# Sheet1.net
KiCad netlist of a schematic drawn in Altium Designer
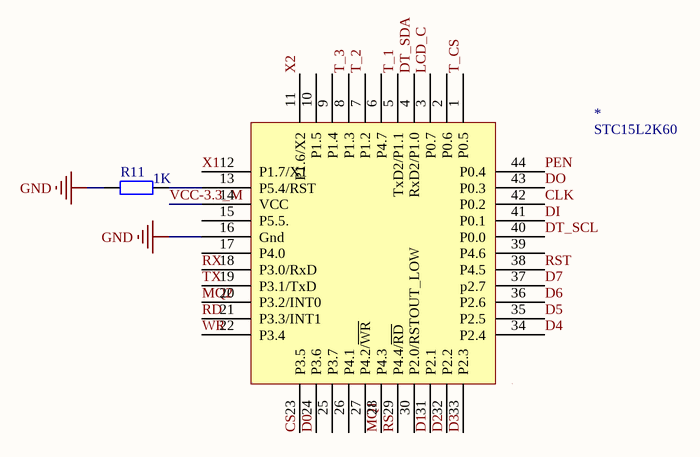
[diagram p0: Sheet1.SchDoc]

(export (version "E")
  (design (tool "Eeschema 10.0.6"))
  (components
    (comp (ref "*")
      (value "STC15L2K60")
      (description "STC15L,44pin")
      (libsource (lib "MySch") (part "STC15L2K60"))
    )
    (comp (ref "R11")
      (value "1K")
      (footprint "AXIAL-0.4")
      (description "Resistor")
      (fields (field (name "PUBLISHER") "Altium Limited"))
      (libsource (lib "Miscellaneous Devices") (part "Res2"))
    )
  )
  (nets
    (net (code "1") (name "/CLK") (class "Default")
      (node (ref "*") (pin "42") (pinfunction "P0.2_42") (pintype "passive"))
    )
    (net (code "2") (name "/CS") (class "Default")
      (node (ref "*") (pin "23") (pinfunction "P3.5_23") (pintype "passive"))
    )
    (net (code "3") (name "/D0") (class "Default")
      (node (ref "*") (pin "24") (pinfunction "P3.6_24") (pintype "passive"))
    )
    (net (code "4") (name "/D1") (class "Default")
      (node (ref "*") (pin "31") (pinfunction "P2.1_31") (pintype "passive"))
    )
    (net (code "5") (name "/D2") (class "Default")
      (node (ref "*") (pin "32") (pinfunction "P2.2_32") (pintype "passive"))
    )
    (net (code "6") (name "/D3") (class "Default")
      (node (ref "*") (pin "33") (pinfunction "P2.3_33") (pintype "passive"))
    )
    (net (code "7") (name "/D4") (class "Default")
      (node (ref "*") (pin "34") (pinfunction "P2.4_34") (pintype "passive"))
    )
    (net (code "8") (name "/D5") (class "Default")
      (node (ref "*") (pin "35") (pinfunction "P2.5_35") (pintype "passive"))
    )
    (net (code "9") (name "/D6") (class "Default")
      (node (ref "*") (pin "36") (pinfunction "P2.6_36") (pintype "passive"))
    )
    (net (code "10") (name "/D7") (class "Default")
      (node (ref "*") (pin "37") (pinfunction "p2.7_37") (pintype "passive"))
    )
    (net (code "11") (name "/DI") (class "Default")
      (node (ref "*") (pin "41") (pinfunction "P0.1_41") (pintype "passive"))
    )
    (net (code "12") (name "/DO") (class "Default")
      (node (ref "*") (pin "43") (pinfunction "P0.3_43") (pintype "passive"))
    )
    (net (code "13") (name "/DT_SCL") (class "Default")
      (node (ref "*") (pin "40") (pinfunction "P0.0_40") (pintype "passive"))
    )
    (net (code "14") (name "/DT_SDA") (class "Default")
      (node (ref "*") (pin "4") (pinfunction "RxD2/P1.0_4") (pintype "passive"))
    )
    (net (code "15") (name "/LCD_C") (class "Default")
      (node (ref "*") (pin "3") (pinfunction "P0.7_3") (pintype "passive"))
    )
    (net (code "16") (name "/MQ1") (class "Default")
      (node (ref "*") (pin "28") (pinfunction "P4.3_28") (pintype "passive"))
    )
    (net (code "17") (name "/MQ2") (class "Default")
      (node (ref "*") (pin "20") (pinfunction "P3.2/INT0_20") (pintype "passive"))
    )
    (net (code "18") (name "/PEN") (class "Default")
      (node (ref "*") (pin "44") (pinfunction "P0.4_44") (pintype "passive"))
    )
    (net (code "19") (name "/RD") (class "Default")
      (node (ref "*") (pin "21") (pinfunction "P3.3/INT1_21") (pintype "passive"))
    )
    (net (code "20") (name "/RS") (class "Default")
      (node (ref "*") (pin "29") (pinfunction "P4.4/~{RD}_29") (pintype "passive"))
    )
    (net (code "21") (name "/RST") (class "Default")
      (node (ref "*") (pin "38") (pinfunction "P4.5_38") (pintype "passive"))
    )
    (net (code "22") (name "/RX") (class "Default")
      (node (ref "*") (pin "18") (pinfunction "P3.0/RxD_18") (pintype "passive"))
    )
    (net (code "23") (name "/TX") (class "Default")
      (node (ref "*") (pin "19") (pinfunction "P3.1/TxD_19") (pintype "passive"))
    )
    (net (code "24") (name "/T_1") (class "Default")
      (node (ref "*") (pin "5") (pinfunction "TxD2/P1.1_5") (pintype "passive"))
    )
    (net (code "25") (name "/T_2") (class "Default")
      (node (ref "*") (pin "7") (pinfunction "P1.2_7") (pintype "passive"))
    )
    (net (code "26") (name "/T_3") (class "Default")
      (node (ref "*") (pin "8") (pinfunction "P1.3_8") (pintype "passive"))
    )
    (net (code "27") (name "/T_CS") (class "Default")
      (node (ref "*") (pin "1") (pinfunction "P0.5_1") (pintype "passive"))
    )
    (net (code "28") (name "/VCC-3.3_M") (class "Default")
      (node (ref "*") (pin "14") (pinfunction "VCC_14") (pintype "passive"))
    )
    (net (code "29") (name "/WR") (class "Default")
      (node (ref "*") (pin "22") (pinfunction "P3.4_22") (pintype "passive"))
    )
    (net (code "30") (name "/X1") (class "Default")
      (node (ref "*") (pin "12") (pinfunction "P1.7/X1_12") (pintype "passive"))
    )
    (net (code "31") (name "/X2") (class "Default")
      (node (ref "*") (pin "11") (pinfunction "P1.6/X2_11") (pintype "passive"))
    )
    (net (code "32") (name "GND") (class "Default")
      (node (ref "*") (pin "16") (pinfunction "Gnd_16") (pintype "passive"))
      (node (ref "R11") (pin "1") (pinfunction "1_1") (pintype "passive"))
    )
    (net (code "33") (name "Net-(*-P5.4{slash}RST)") (class "Default")
      (node (ref "*") (pin "13") (pinfunction "P5.4/RST_13") (pintype "passive"))
      (node (ref "R11") (pin "2") (pinfunction "2_2") (pintype "passive"))
    )
    (net (code "34") (name "unconnected-(*-P0.6-Pad2)") (class "Default")
      (node (ref "*") (pin "2") (pinfunction "P0.6_2") (pintype "passive"))
    )
    (net (code "35") (name "unconnected-(*-P1.4-Pad9)") (class "Default")
      (node (ref "*") (pin "9") (pinfunction "P1.4_9") (pintype "passive"))
    )
    (net (code "36") (name "unconnected-(*-P1.5-Pad10)") (class "Default")
      (node (ref "*") (pin "10") (pinfunction "P1.5_10") (pintype "passive"))
    )
    (net (code "37") (name "unconnected-(*-P2.0{slash}RSTOUT_LOW-Pad30)") (class "Default")
      (node (ref "*") (pin "30") (pinfunction "P2.0/RSTOUT_LOW_30") (pintype "passive"))
    )
    (net (code "38") (name "unconnected-(*-P3.7-Pad25)") (class "Default")
      (node (ref "*") (pin "25") (pinfunction "P3.7_25") (pintype "passive"))
    )
    (net (code "39") (name "unconnected-(*-P4.0-Pad17)") (class "Default")
      (node (ref "*") (pin "17") (pinfunction "P4.0_17") (pintype "passive"))
    )
    (net (code "40") (name "unconnected-(*-P4.1-Pad26)") (class "Default")
      (node (ref "*") (pin "26") (pinfunction "P4.1_26") (pintype "passive"))
    )
    (net (code "41") (name "unconnected-(*-P4.2{slash}~{WR}-Pad27)") (class "Default")
      (node (ref "*") (pin "27") (pinfunction "P4.2/~{WR}_27") (pintype "passive"))
    )
    (net (code "42") (name "unconnected-(*-P4.6-Pad39)") (class "Default")
      (node (ref "*") (pin "39") (pinfunction "P4.6_39") (pintype "passive"))
    )
    (net (code "43") (name "unconnected-(*-P4.7-Pad6)") (class "Default")
      (node (ref "*") (pin "6") (pinfunction "P4.7_6") (pintype "passive"))
    )
    (net (code "44") (name "unconnected-(*-P5.5.-Pad15)") (class "Default")
      (node (ref "*") (pin "15") (pinfunction "P5.5._15") (pintype "passive"))
    )
  )
)
